# greenscreamer_redraw.net
KiCad netlist of a schematic drawn in EAGLE
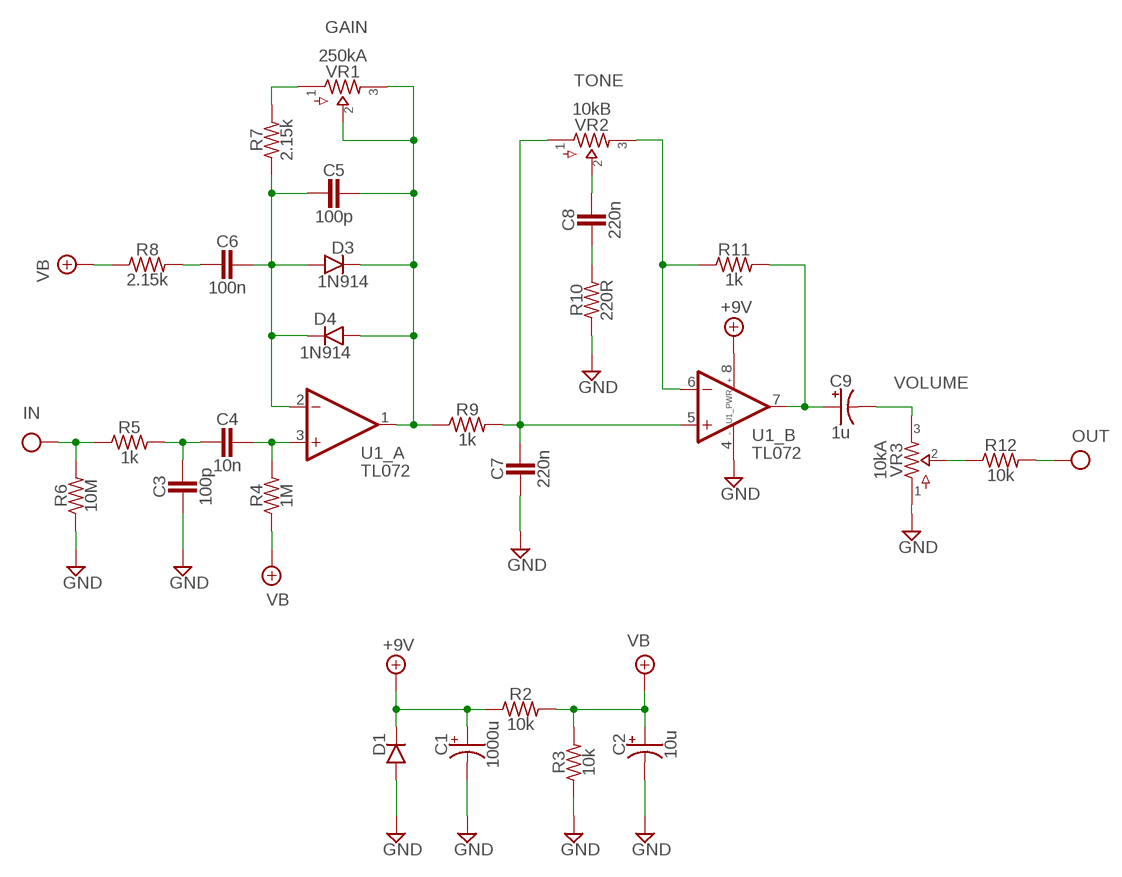
[diagram p0: schematic, sheet 1]

(export (version "E")
  (design (tool "Eeschema 10.0.6"))
  (components
    (comp (ref "C1")
      (value "1000u")
      (footprint "eagle-import:050_020")
      (libsource (lib "eagle-import") (part "0500"))
    )
    (comp (ref "C2")
      (value "10u")
      (footprint "eagle-import:050_020")
      (libsource (lib "eagle-import") (part "0500"))
    )
    (comp (ref "C3")
      (value "100p")
      (footprint "eagle-import:BOX_SMALL")
      (libsource (lib "eagle-import") (part "CER/FILMBOX.1"))
    )
    (comp (ref "C4")
      (value "10n")
      (footprint "eagle-import:BOX_SMALL")
      (libsource (lib "eagle-import") (part "CER/FILMBOX.1"))
    )
    (comp (ref "C5")
      (value "100p")
      (footprint "eagle-import:BOX_SMALL")
      (libsource (lib "eagle-import") (part "CER/FILMBOX.1"))
    )
    (comp (ref "C6")
      (value "100n")
      (footprint "eagle-import:BOX_SMALL")
      (libsource (lib "eagle-import") (part "CER/FILMBOX.1"))
    )
    (comp (ref "C7")
      (value "220n")
      (footprint "eagle-import:BOX_SMALL")
      (libsource (lib "eagle-import") (part "CER/FILMBOX.1"))
    )
    (comp (ref "C8")
      (value "220n")
      (footprint "eagle-import:BOX_SMALL")
      (libsource (lib "eagle-import") (part "CER/FILMBOX.1"))
    )
    (comp (ref "C9")
      (value "1u")
      (footprint "eagle-import:050_020")
      (libsource (lib "eagle-import") (part "0500"))
    )
    (comp (ref "D1")
      (value "DO35.2")
      (footprint "eagle-import:DO35-2")
      (libsource (lib "eagle-import") (part "DO35.2"))
    )
    (comp (ref "D3")
      (value "1N914")
      (footprint "eagle-import:DO35-2")
      (libsource (lib "eagle-import") (part "DO35.2"))
    )
    (comp (ref "D4")
      (value "1N914")
      (footprint "eagle-import:DO35-2")
      (libsource (lib "eagle-import") (part "DO35.2"))
    )
    (comp (ref "R2")
      (value "10k")
      (footprint "eagle-import:R0207_3")
      (libsource (lib "eagle-import") (part "R_.3B"))
    )
    (comp (ref "R3")
      (value "10k")
      (footprint "eagle-import:R0207_3")
      (libsource (lib "eagle-import") (part "R_.3B"))
    )
    (comp (ref "R4")
      (value "1M")
      (footprint "eagle-import:R0207_3")
      (libsource (lib "eagle-import") (part "R_.3B"))
    )
    (comp (ref "R5")
      (value "1k")
      (footprint "eagle-import:R0207_3")
      (libsource (lib "eagle-import") (part "R_.3B"))
    )
    (comp (ref "R6")
      (value "10M")
      (footprint "eagle-import:R0207_3")
      (libsource (lib "eagle-import") (part "R_.3B"))
    )
    (comp (ref "R7")
      (value "2.15k")
      (footprint "eagle-import:R0207_3")
      (libsource (lib "eagle-import") (part "R_.3B"))
    )
    (comp (ref "R8")
      (value "2.15k")
      (footprint "eagle-import:R0207_3")
      (libsource (lib "eagle-import") (part "R_.3B"))
    )
    (comp (ref "R9")
      (value "1k")
      (footprint "eagle-import:R0207_3")
      (libsource (lib "eagle-import") (part "R_.3B"))
    )
    (comp (ref "R10")
      (value "220R")
      (footprint "eagle-import:R0207_3")
      (libsource (lib "eagle-import") (part "R_.3B"))
    )
    (comp (ref "R11")
      (value "1k")
      (footprint "eagle-import:R0207_3")
      (libsource (lib "eagle-import") (part "R_.3B"))
    )
    (comp (ref "R12")
      (value "10k")
      (footprint "eagle-import:R0207_3")
      (libsource (lib "eagle-import") (part "R_.3B"))
    )
    (comp (ref "U1")
      (value "TL072")
      (footprint "eagle-import:DIL0")
      (libsource (lib "eagle-import") (part "DUALTH"))
    )
    (comp (ref "VR1")
      (value "250kA")
      (footprint "eagle-import:16MM")
      (libsource (lib "eagle-import") (part "POTS16MM"))
    )
    (comp (ref "VR2")
      (value "10kB")
      (footprint "eagle-import:16MM")
      (libsource (lib "eagle-import") (part "POTS16MM"))
    )
    (comp (ref "VR3")
      (value "10kA")
      (footprint "eagle-import:16MM")
      (libsource (lib "eagle-import") (part "POTS16MM"))
    )
  )
  (nets
    (net (code "1") (name "+9V") (class "Default")
      (node (ref "C1") (pin "+") (pinfunction "+_+") (pintype "passive"))
      (node (ref "D1") (pin "C") (pinfunction "C_C") (pintype "passive"))
      (node (ref "R2") (pin "1") (pinfunction "1_1") (pintype "passive"))
      (node (ref "U1") (pin "8") (pinfunction "V+_8") (pintype "power_in"))
    )
    (net (code "2") (name "GND") (class "Default")
      (node (ref "C1") (pin "-") (pinfunction "-_-") (pintype "passive"))
      (node (ref "C2") (pin "-") (pinfunction "-_-") (pintype "passive"))
      (node (ref "C3") (pin "2") (pinfunction "2_2") (pintype "passive"))
      (node (ref "C7") (pin "2") (pinfunction "2_2") (pintype "passive"))
      (node (ref "D1") (pin "A") (pinfunction "A_A") (pintype "passive"))
      (node (ref "R10") (pin "1") (pinfunction "1_1") (pintype "passive"))
      (node (ref "R3") (pin "1") (pinfunction "1_1") (pintype "passive"))
      (node (ref "R6") (pin "1") (pinfunction "1_1") (pintype "passive"))
      (node (ref "U1") (pin "4") (pinfunction "V-_4") (pintype "power_in"))
      (node (ref "VR3") (pin "1") (pinfunction "1_1") (pintype "passive"))
    )
    (net (code "3") (name "IN") (class "Default")
      (node (ref "R5") (pin "1") (pinfunction "1_1") (pintype "passive"))
      (node (ref "R6") (pin "2") (pinfunction "2_2") (pintype "passive"))
    )
    (net (code "4") (name "Net-(C3-Pad1)") (class "Default")
      (node (ref "C3") (pin "1") (pinfunction "1_1") (pintype "passive"))
      (node (ref "C4") (pin "2") (pinfunction "2_2") (pintype "passive"))
      (node (ref "R5") (pin "2") (pinfunction "2_2") (pintype "passive"))
    )
    (net (code "5") (name "Net-(C6-Pad2)") (class "Default")
      (node (ref "C6") (pin "2") (pinfunction "2_2") (pintype "passive"))
      (node (ref "R8") (pin "2") (pinfunction "2_2") (pintype "passive"))
    )
    (net (code "6") (name "Net-(C8-Pad1)") (class "Default")
      (node (ref "C8") (pin "1") (pinfunction "1_1") (pintype "passive"))
      (node (ref "VR2") (pin "2") (pinfunction "2_2") (pintype "passive"))
    )
    (net (code "7") (name "Net-(C8-Pad2)") (class "Default")
      (node (ref "C8") (pin "2") (pinfunction "2_2") (pintype "passive"))
      (node (ref "R10") (pin "2") (pinfunction "2_2") (pintype "passive"))
    )
    (net (code "8") (name "Net-(C9-Pad-)") (class "Default")
      (node (ref "C9") (pin "-") (pinfunction "-_-") (pintype "passive"))
      (node (ref "VR3") (pin "3") (pinfunction "3_3") (pintype "passive"))
    )
    (net (code "9") (name "Net-(R7-Pad2)") (class "Default")
      (node (ref "R7") (pin "2") (pinfunction "2_2") (pintype "passive"))
      (node (ref "VR1") (pin "1") (pinfunction "1_1") (pintype "passive"))
    )
    (net (code "10") (name "Net-(R12-Pad1)") (class "Default")
      (node (ref "R12") (pin "1") (pinfunction "1_1") (pintype "passive"))
      (node (ref "VR3") (pin "2") (pinfunction "2_2") (pintype "passive"))
    )
    (net (code "11") (name "Net-(U1A-+IN)") (class "Default")
      (node (ref "C4") (pin "1") (pinfunction "1_1") (pintype "passive"))
      (node (ref "R4") (pin "2") (pinfunction "2_2") (pintype "passive"))
      (node (ref "U1") (pin "3") (pinfunction "+IN_3") (pintype "input"))
    )
    (net (code "12") (name "Net-(U1A--IN)") (class "Default")
      (node (ref "C5") (pin "2") (pinfunction "2_2") (pintype "passive"))
      (node (ref "C6") (pin "1") (pinfunction "1_1") (pintype "passive"))
      (node (ref "D3") (pin "A") (pinfunction "A_A") (pintype "passive"))
      (node (ref "D4") (pin "C") (pinfunction "C_C") (pintype "passive"))
      (node (ref "R7") (pin "1") (pinfunction "1_1") (pintype "passive"))
      (node (ref "U1") (pin "2") (pinfunction "-IN_2") (pintype "input"))
    )
    (net (code "13") (name "Net-(U1A-OUT)") (class "Default")
      (node (ref "C5") (pin "1") (pinfunction "1_1") (pintype "passive"))
      (node (ref "D3") (pin "C") (pinfunction "C_C") (pintype "passive"))
      (node (ref "D4") (pin "A") (pinfunction "A_A") (pintype "passive"))
      (node (ref "R9") (pin "1") (pinfunction "1_1") (pintype "passive"))
      (node (ref "U1") (pin "1") (pinfunction "OUT_1") (pintype "output"))
      (node (ref "VR1") (pin "2") (pinfunction "2_2") (pintype "passive"))
      (node (ref "VR1") (pin "3") (pinfunction "3_3") (pintype "passive"))
    )
    (net (code "14") (name "Net-(U1B-+IN)") (class "Default")
      (node (ref "C7") (pin "1") (pinfunction "1_1") (pintype "passive"))
      (node (ref "R9") (pin "2") (pinfunction "2_2") (pintype "passive"))
      (node (ref "U1") (pin "5") (pinfunction "+IN_5") (pintype "input"))
      (node (ref "VR2") (pin "1") (pinfunction "1_1") (pintype "passive"))
    )
    (net (code "15") (name "Net-(U1B--IN)") (class "Default")
      (node (ref "R11") (pin "1") (pinfunction "1_1") (pintype "passive"))
      (node (ref "U1") (pin "6") (pinfunction "-IN_6") (pintype "input"))
      (node (ref "VR2") (pin "3") (pinfunction "3_3") (pintype "passive"))
    )
    (net (code "16") (name "Net-(U1B-OUT)") (class "Default")
      (node (ref "C9") (pin "+") (pinfunction "+_+") (pintype "passive"))
      (node (ref "R11") (pin "2") (pinfunction "2_2") (pintype "passive"))
      (node (ref "U1") (pin "7") (pinfunction "OUT_7") (pintype "output"))
    )
    (net (code "17") (name "OUT") (class "Default")
      (node (ref "R12") (pin "2") (pinfunction "2_2") (pintype "passive"))
    )
    (net (code "18") (name "VB") (class "Default")
      (node (ref "C2") (pin "+") (pinfunction "+_+") (pintype "passive"))
      (node (ref "R2") (pin "2") (pinfunction "2_2") (pintype "passive"))
      (node (ref "R3") (pin "2") (pinfunction "2_2") (pintype "passive"))
      (node (ref "R4") (pin "1") (pinfunction "1_1") (pintype "passive"))
      (node (ref "R8") (pin "1") (pinfunction "1_1") (pintype "passive"))
    )
  )
)
